# XO_125M.net
KiCad netlist of a schematic drawn in Altium Designer
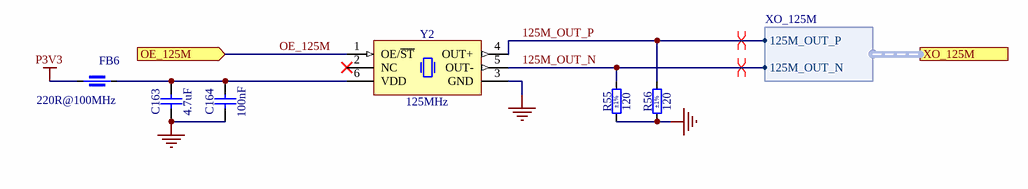
[diagram p0: XO_125M.SchDoc]

(export (version "E")
  (design (tool "Eeschema 10.0.6"))
  (components
    (comp (ref "C163")
      (value "4.7uF")
      (footprint "CAPC1005X55N")
      (description "Non-polarised capacitor")
      (fields
        (field (name "PART NUMBER") "CC0402_4.7UF_6.3V_20%_X5R")
        (field (name "VOLTAGE") "6.3V")
        (field (name "AUTHOR") "CERN DEM JLC")
      )
      (libsource (lib "Capacitors") (part "Capacitor - non polarized"))
    )
    (comp (ref "C164")
      (value "100nF")
      (footprint "CAPC0603X33N")
      (description "Non-polarised capacitor")
      (fields
        (field (name "PART NUMBER") "CC0201_100NF_6.3V_10%_X5R")
        (field (name "VOLTAGE") "6.3V")
        (field (name "AUTHOR") "CERN DEM JLC")
      )
      (libsource (lib "Capacitors") (part "Capacitor - non polarized"))
    )
    (comp (ref "FB6")
      (value "220R@100MHz")
      (footprint "INDC1608X95N")
      (fields
        (field (name "TOLERANCE") "±25%")
        (field (name "PART NUMBER") "IND0603_MURATA_BLM18SG221TN1")
        (field (name "POWER") "2.5A")
        (field (name "AUTHOR") "CERN DEM MR")
      )
      (libsource (lib "Inductors & Transformers") (part "Ferrite Bead"))
    )
    (comp (ref "R55")
      (value "120")
      (footprint "RESC1005X40N")
      (description "Resistor - 1%")
      (fields
        (field (name "TOLERANCE") "±1%")
        (field (name "PART NUMBER") "R0402_120R_1%_0.0625W_100PPM")
        (field (name "POWER") "0.0625W")
        (field (name "AUTHOR") "CERN DEM JLC")
      )
      (libsource (lib "Resistors") (part "Resistor - 1%"))
    )
    (comp (ref "R56")
      (value "120")
      (footprint "RESC1005X40N")
      (description "Resistor - 1%")
      (fields
        (field (name "TOLERANCE") "±1%")
        (field (name "PART NUMBER") "R0402_120R_1%_0.0625W_100PPM")
        (field (name "POWER") "0.0625W")
        (field (name "AUTHOR") "CERN DEM JLC")
      )
      (libsource (lib "Resistors") (part "Resistor - 1%"))
    )
    (comp (ref "Y2")
      (value "125MHz")
      (footprint "OSC_SI-TIME_SIT9121-C")
      (description "Standard Frequency Differential Oscillator")
      (fields
        (field (name "PART NUMBER") "OSC_125MHZ_SI-TIME_SIT9121AI-2C2-33E125.000000")
        (field (name "MANUFACTURER") "SI TIME")
        (field (name "AUTHOR") "CERN DEM HF")
      )
      (libsource (lib "ICs And Semiconductors") (part "Oscillator SI-TIME_SIT9121"))
    )
  )
  (nets
    (net (code "2") (name "/125M_OUT_N") (class "Default")
      (node (ref "R55") (pin "2") (pinfunction "2_2") (pintype "passive"))
      (node (ref "Y2") (pin "5") (pinfunction "OUT-_5") (pintype "output"))
    )
    (net (code "3") (name "/125M_OUT_P") (class "Default")
      (node (ref "R56") (pin "2") (pinfunction "2_2") (pintype "passive"))
      (node (ref "Y2") (pin "4") (pinfunction "OUT+_4") (pintype "output"))
    )
    (net (code "4") (name "/OE_125M") (class "Default")
      (node (ref "Y2") (pin "1") (pinfunction "OE/~{ST}_1") (pintype "input"))
    )
    (net (code "6") (name "GND") (class "Default")
      (node (ref "C163") (pin "1") (pinfunction "1_1") (pintype "passive"))
      (node (ref "C164") (pin "1") (pinfunction "1_1") (pintype "passive"))
      (node (ref "R55") (pin "1") (pinfunction "1_1") (pintype "passive"))
      (node (ref "R56") (pin "1") (pinfunction "1_1") (pintype "passive"))
      (node (ref "Y2") (pin "3") (pinfunction "GND_3") (pintype "power_in"))
    )
    (net (code "7") (name "Net-(Y2-VDD)") (class "Default")
      (node (ref "C163") (pin "2") (pinfunction "2_2") (pintype "passive"))
      (node (ref "C164") (pin "2") (pinfunction "2_2") (pintype "passive"))
      (node (ref "FB6") (pin "2") (pinfunction "2_2") (pintype "passive"))
      (node (ref "Y2") (pin "6") (pinfunction "VDD_6") (pintype "power_in"))
    )
    (net (code "8") (name "P3V3") (class "Default")
      (node (ref "FB6") (pin "1") (pinfunction "1_1") (pintype "passive"))
    )
    (net (code "9") (name "unconnected-(Y2-NC-Pad2)") (class "Default")
      (node (ref "Y2") (pin "2") (pinfunction "NC_2") (pintype "passive+no_connect"))
    )
  )
)
